# bandmodule-160m.net
KiCad netlist of a schematic drawn in EAGLE
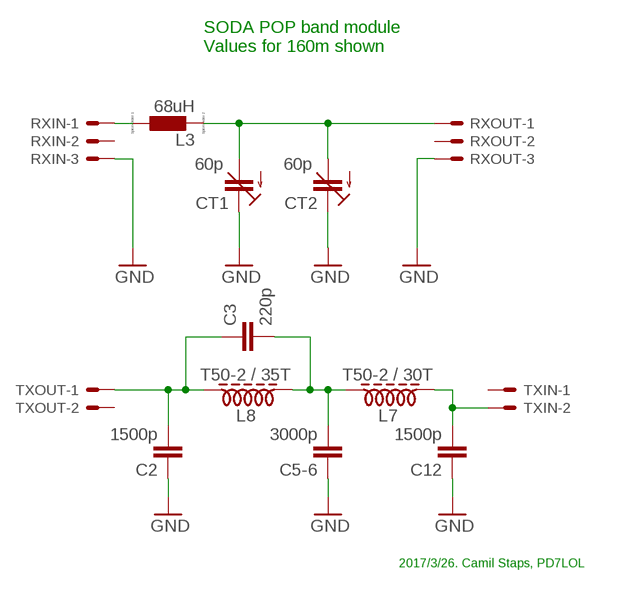
[diagram p0: schematic, sheet 1]

(export (version "E")
  (design (tool "Eeschema 10.0.6"))
  (components
    (comp (ref "C2")
      (value "1500p")
      (footprint "eagle-import:C5B2.5")
      (libsource (lib "eagle-import") (part "C5/2.5"))
    )
    (comp (ref "C3")
      (value "220p")
      (footprint "eagle-import:C5B2.5")
      (libsource (lib "eagle-import") (part "C5/2.5"))
    )
    (comp (ref "C5-6")
      (value "3000p")
      (footprint "eagle-import:C5B2.5")
      (libsource (lib "eagle-import") (part "C5/2.5"))
    )
    (comp (ref "C12")
      (value "1500p")
      (footprint "eagle-import:C5B2.5")
      (libsource (lib "eagle-import") (part "C5/2.5"))
    )
    (comp (ref "CT1")
      (value "60p")
      (footprint "eagle-import:CTRIMTZ03")
      (libsource (lib "eagle-import") (part "C-TRIMMTZ03"))
    )
    (comp (ref "CT2")
      (value "60p")
      (footprint "eagle-import:CTRIMTZ03")
      (libsource (lib "eagle-import") (part "C-TRIMMTZ03"))
    )
    (comp (ref "L3")
      (value "68uH")
      (footprint "eagle-import:0207_10")
      (libsource (lib "eagle-import") (part "L0207/10"))
    )
    (comp (ref "L7")
      (value "T50-2 / 30T")
      (footprint "eagle-import:T30-2-28AWG-15T")
      (libsource (lib "eagle-import") (part "INDUCTORT30-2-28AWG-15T"))
    )
    (comp (ref "L8")
      (value "T50-2 / 35T")
      (footprint "eagle-import:T30-2-28AWG-15T")
      (libsource (lib "eagle-import") (part "INDUCTORT30-2-28AWG-15T"))
    )
    (comp (ref "RXIN")
      (value "22-23-2031")
      (footprint "eagle-import:22-23-2031")
      (fields (field (name "MF") "MOLEX"))
      (libsource (lib "eagle-import") (part "22-23-2031"))
    )
    (comp (ref "RXOUT")
      (value "22-23-2031")
      (footprint "eagle-import:22-23-2031")
      (fields (field (name "MF") "MOLEX"))
      (libsource (lib "eagle-import") (part "22-23-2031"))
    )
    (comp (ref "TXIN")
      (value "22-23-2021")
      (footprint "eagle-import:22-23-2021")
      (fields (field (name "MF") "MOLEX"))
      (libsource (lib "eagle-import") (part "22-23-2021"))
    )
    (comp (ref "TXOUT")
      (value "22-23-2021")
      (footprint "eagle-import:22-23-2021")
      (fields (field (name "MF") "MOLEX"))
      (libsource (lib "eagle-import") (part "22-23-2021"))
    )
  )
  (nets
    (net (code "1") (name "GND") (class "Default")
      (node (ref "C12") (pin "1") (pinfunction "1_1") (pintype "passive"))
      (node (ref "C2") (pin "1") (pinfunction "1_1") (pintype "passive"))
      (node (ref "C5-6") (pin "1") (pinfunction "1_1") (pintype "passive"))
      (node (ref "CT1") (pin "1") (pinfunction "E_1") (pintype "passive"))
      (node (ref "CT2") (pin "1") (pinfunction "E_1") (pintype "passive"))
      (node (ref "RXIN") (pin "3") (pinfunction "S_3") (pintype "passive"))
      (node (ref "RXOUT") (pin "3") (pinfunction "S_3") (pintype "passive"))
    )
    (net (code "2") (name "Net-(CT1-A)") (class "Default")
      (node (ref "CT1") (pin "2") (pinfunction "A_2") (pintype "passive"))
      (node (ref "CT2") (pin "2") (pinfunction "A_2") (pintype "passive"))
      (node (ref "L3") (pin "2") (pinfunction "2_2") (pintype "passive"))
      (node (ref "RXOUT") (pin "1") (pinfunction "S_1") (pintype "passive"))
    )
    (net (code "3") (name "Net-(L7-1)") (class "Default")
      (node (ref "C12") (pin "2") (pinfunction "2_2") (pintype "passive"))
      (node (ref "L7") (pin "P$1") (pinfunction "1_P$1") (pintype "passive"))
      (node (ref "TXIN") (pin "2") (pinfunction "S_2") (pintype "passive"))
    )
    (net (code "4") (name "Net-(L7-2)") (class "Default")
      (node (ref "C3") (pin "2") (pinfunction "2_2") (pintype "passive"))
      (node (ref "C5-6") (pin "2") (pinfunction "2_2") (pintype "passive"))
      (node (ref "L7") (pin "P$2") (pinfunction "2_P$2") (pintype "passive"))
      (node (ref "L8") (pin "P$1") (pinfunction "1_P$1") (pintype "passive"))
    )
    (net (code "5") (name "Net-(L8-2)") (class "Default")
      (node (ref "C2") (pin "2") (pinfunction "2_2") (pintype "passive"))
      (node (ref "C3") (pin "1") (pinfunction "1_1") (pintype "passive"))
      (node (ref "L8") (pin "P$2") (pinfunction "2_P$2") (pintype "passive"))
      (node (ref "TXOUT") (pin "1") (pinfunction "S_1") (pintype "passive"))
    )
    (net (code "6") (name "Net-(RXINA-S)") (class "Default")
      (node (ref "L3") (pin "1") (pinfunction "1_1") (pintype "passive"))
      (node (ref "RXIN") (pin "1") (pinfunction "S_1") (pintype "passive"))
    )
    (net (code "7") (name "unconnected-(RXINB-S-Pad2)") (class "Default")
      (node (ref "RXIN") (pin "2") (pinfunction "S_2") (pintype "passive"))
    )
    (net (code "8") (name "unconnected-(RXOUTB-S-Pad2)") (class "Default")
      (node (ref "RXOUT") (pin "2") (pinfunction "S_2") (pintype "passive"))
    )
    (net (code "9") (name "unconnected-(TXINA-S-Pad1)") (class "Default")
      (node (ref "TXIN") (pin "1") (pinfunction "S_1") (pintype "passive"))
    )
    (net (code "10") (name "unconnected-(TXOUTB-S-Pad2)") (class "Default")
      (node (ref "TXOUT") (pin "2") (pinfunction "S_2") (pintype "passive"))
    )
  )
)
